# Transmitter_MD.net
KiCad netlist of a schematic drawn in Altium Designer
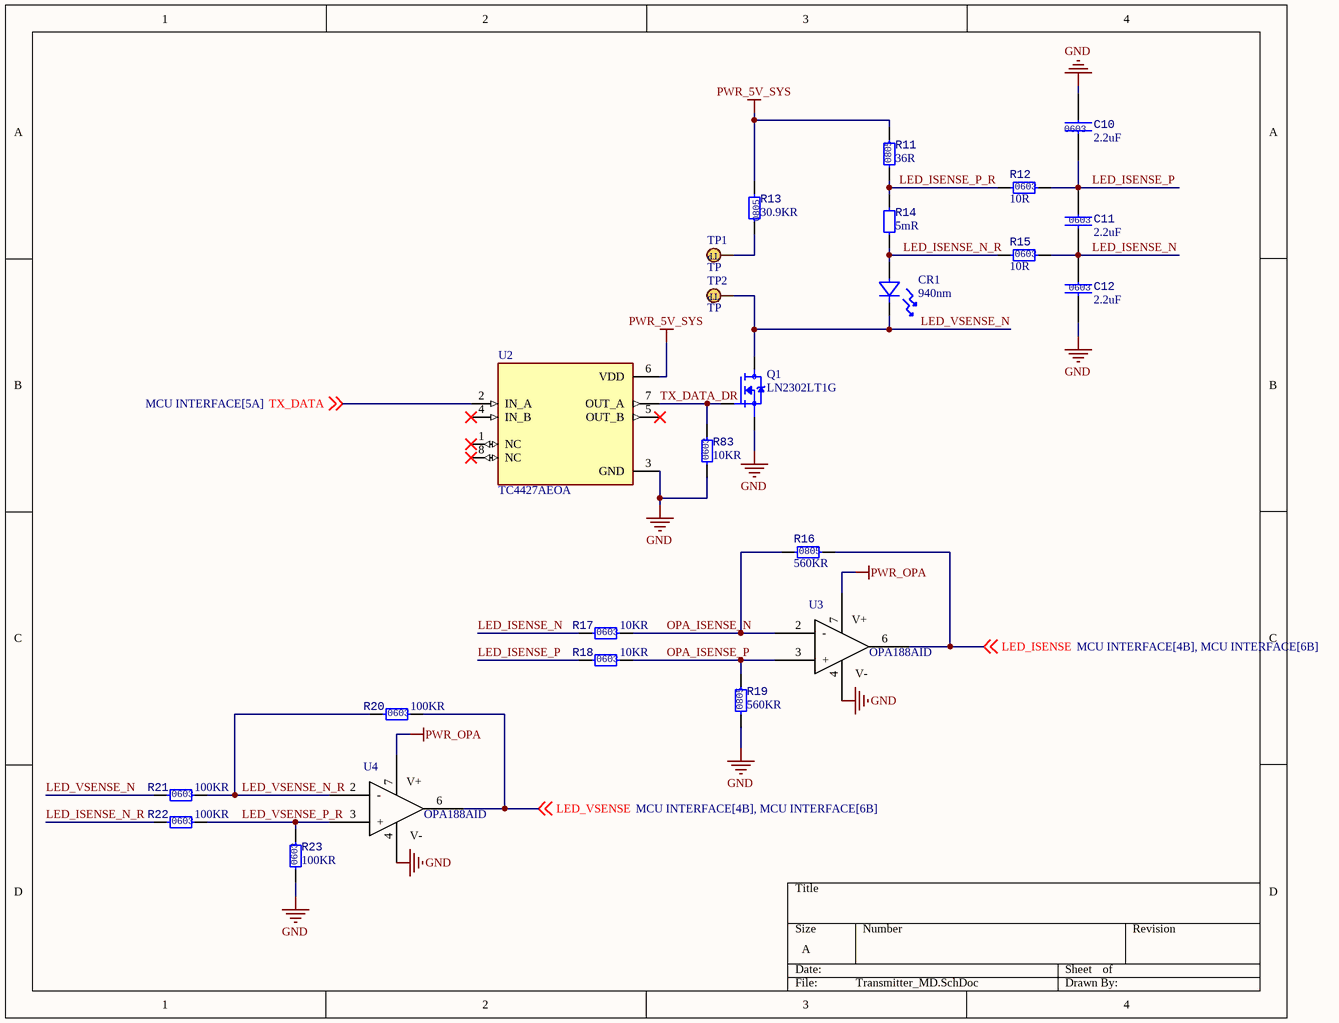
[diagram p0: Transmitter_MD.SchDoc]

(export (version "E")
  (design (tool "Eeschema 10.0.6"))
  (components
    (comp (ref "C10")
      (value "2.2uF")
      (footprint "CAPCER 0603 SMD")
      (description "Tụ Gốm 0603 2.2uF 50V")
      (fields (field (name "SIZE") "0603"))
      (libsource (lib "Database_Libs2") (part "CAPACITOR"))
    )
    (comp (ref "C11")
      (value "2.2uF")
      (footprint "CAPCER 0603 SMD")
      (description "Tụ Gốm 0603 2.2uF 50V")
      (fields (field (name "SIZE") "0603"))
      (libsource (lib "Database_Libs2") (part "CAPACITOR"))
    )
    (comp (ref "C12")
      (value "2.2uF")
      (footprint "CAPCER 0603 SMD")
      (description "Tụ Gốm 0603 2.2uF 50V")
      (fields (field (name "SIZE") "0603"))
      (libsource (lib "Database_Libs2") (part "CAPACITOR"))
    )
    (comp (ref "CR1")
      (value "940nm")
      (footprint "TSAL6100")
      (fields (field (name "Comment") "LED IR 940nm"))
      (libsource (lib "Database_Libs2") (part "TSAL6100"))
    )
    (comp (ref "Q1")
      (value "LN2302LT1G")
      (footprint "SOT23-3")
      (description "LN2302LT1G MOSFET Kênh N 20V 2.3A SOT-23-3")
      (fields (field (name "Comment") "NMOS"))
      (libsource (lib "Database_Libs2") (part "N_MOS"))
    )
    (comp (ref "R11")
      (value "36R")
      (footprint "RESC 0805 SMD")
      (fields (field (name "SIZE") "0805"))
      (libsource (lib "") (part "RESISTOR_1"))
    )
    (comp (ref "R12")
      (value "10R")
      (footprint "RESC 0603(1608) SMD")
      (description "Điện Trở 10 Ohm 0603 1%")
      (fields (field (name "SIZE") "0603"))
      (libsource (lib "Database_Libs2") (part "RESISTOR"))
    )
    (comp (ref "R13")
      (value "30.9KR")
      (footprint "RESC 0805 SMD")
      (description "Điện Trở 30.9 KOhm 0805 1%")
      (fields (field (name "SIZE") "0805"))
      (libsource (lib "") (part "RESISTOR_2"))
    )
    (comp (ref "R14") (value "5mR") (footprint "RS_P10_D1P5") (libsource (lib "") (part "RESISTOR_1")))
    (comp (ref "R15")
      (value "10R")
      (footprint "RESC 0603(1608) SMD")
      (description "Điện Trở 10 Ohm 0603 1%")
      (fields (field (name "SIZE") "0603"))
      (libsource (lib "Database_Libs2") (part "RESISTOR"))
    )
    (comp (ref "R16")
      (value "560KR")
      (footprint "RESC 0805 SMD")
      (fields (field (name "SIZE") "0805"))
      (libsource (lib "Database_Libs2") (part "RESISTOR"))
    )
    (comp (ref "R17")
      (value "10KR")
      (footprint "RESC 0603(1608) SMD")
      (description "RESISTOR SMD 10KR OHM 1% 100mW 0603")
      (fields (field (name "SIZE") "0603") (field (name "TOLERANCE") "1%"))
      (libsource (lib "Database_Libs1") (part "RESISTOR"))
    )
    (comp (ref "R18")
      (value "10KR")
      (footprint "RESC 0603(1608) SMD")
      (description "RESISTOR SMD 10KR OHM 1% 100mW 0603")
      (fields (field (name "SIZE") "0603") (field (name "TOLERANCE") "1%"))
      (libsource (lib "Database_Libs1") (part "RESISTOR"))
    )
    (comp (ref "R19")
      (value "560KR")
      (footprint "RESC 0805 SMD")
      (fields (field (name "SIZE") "0805"))
      (libsource (lib "") (part "RESISTOR_1"))
    )
    (comp (ref "R20")
      (value "100KR")
      (footprint "RESC 0603(1608) SMD")
      (description "RESISTOR SMD 100KR OHM 1% 100mW 0603")
      (fields (field (name "SIZE") "0603") (field (name "TOLERANCE") "1%"))
      (libsource (lib "Database_Libs1") (part "RESISTOR"))
    )
    (comp (ref "R21")
      (value "100KR")
      (footprint "RESC 0603(1608) SMD")
      (description "RESISTOR SMD 100KR OHM 1% 100mW 0603")
      (fields (field (name "SIZE") "0603") (field (name "TOLERANCE") "1%"))
      (libsource (lib "Database_Libs1") (part "RESISTOR"))
    )
    (comp (ref "R22")
      (value "100KR")
      (footprint "RESC 0603(1608) SMD")
      (description "RESISTOR SMD 100KR OHM 1% 100mW 0603")
      (fields (field (name "SIZE") "0603") (field (name "TOLERANCE") "1%"))
      (libsource (lib "Database_Libs1") (part "RESISTOR"))
    )
    (comp (ref "R23")
      (value "100KR")
      (footprint "RESC 0603(1608) SMD")
      (description "RESISTOR SMD 100KR OHM 1% 100mW 0603")
      (fields (field (name "SIZE") "0603") (field (name "TOLERANCE") "1%"))
      (libsource (lib "") (part "RESISTOR_1"))
    )
    (comp (ref "R83")
      (value "10KR")
      (footprint "RESC 0603(1608) SMD")
      (description "RESISTOR SMD 10KR OHM 1% 100mW 0603")
      (fields (field (name "SIZE") "0603") (field (name "TOLERANCE") "1%"))
      (libsource (lib "") (part "RESISTOR_1"))
    )
    (comp (ref "TP1")
      (value "TP")
      (footprint "TP_THT_1P0")
      (fields (field (name "Comment") "TEST POINT"))
      (libsource (lib "Database_Libs2") (part "Test_point"))
    )
    (comp (ref "TP2")
      (value "TP")
      (footprint "TP_THT_1P0")
      (fields (field (name "Comment") "TEST POINT"))
      (libsource (lib "Database_Libs2") (part "Test_point"))
    )
    (comp (ref "U2")
      (value "TC4427AEOA")
      (footprint "8-SOIC-OPA")
      (libsource (lib "Database_Libs2") (part "TC4427AEOA"))
    )
    (comp (ref "U3")
      (value "OPA188AID")
      (footprint "8-SOIC-OPA")
      (description "Zero-Drift Amplifier 1 Circuit Rail-to-Rail 8-SOIC")
      (libsource (lib "Database_Libs1") (part "OPA188AID"))
    )
    (comp (ref "U4")
      (value "OPA188AID")
      (footprint "8-SOIC-OPA")
      (description "Zero-Drift Amplifier 1 Circuit Rail-to-Rail 8-SOIC")
      (libsource (lib "Database_Libs1") (part "OPA188AID"))
    )
  )
  (nets
    (net (code "1") (name "/LED_ISENSE_N") (class "Default")
      (node (ref "C11") (pin "2") (pinfunction "2_2") (pintype "passive"))
      (node (ref "C12") (pin "1") (pinfunction "1_1") (pintype "passive"))
      (node (ref "R15") (pin "2") (pinfunction "2_2") (pintype "passive"))
      (node (ref "R17") (pin "1") (pinfunction "1_1") (pintype "passive"))
    )
    (net (code "2") (name "/LED_ISENSE_N_R") (class "Default")
      (node (ref "CR1") (pin "A") (pinfunction "A_A") (pintype "passive"))
      (node (ref "R14") (pin "1") (pinfunction "1_1") (pintype "passive"))
      (node (ref "R15") (pin "1") (pinfunction "1_1") (pintype "passive"))
      (node (ref "R22") (pin "1") (pinfunction "1_1") (pintype "passive"))
    )
    (net (code "3") (name "/LED_ISENSE_P") (class "Default")
      (node (ref "C10") (pin "1") (pinfunction "1_1") (pintype "passive"))
      (node (ref "C11") (pin "1") (pinfunction "1_1") (pintype "passive"))
      (node (ref "R12") (pin "2") (pinfunction "2_2") (pintype "passive"))
      (node (ref "R18") (pin "1") (pinfunction "1_1") (pintype "passive"))
    )
    (net (code "4") (name "/LED_ISENSE_P_R") (class "Default")
      (node (ref "R11") (pin "1") (pinfunction "1_1") (pintype "passive"))
      (node (ref "R12") (pin "1") (pinfunction "1_1") (pintype "passive"))
      (node (ref "R14") (pin "2") (pinfunction "2_2") (pintype "passive"))
    )
    (net (code "5") (name "/LED_VSENSE_N") (class "Default")
      (node (ref "CR1") (pin "K") (pinfunction "K_K") (pintype "passive"))
      (node (ref "Q1") (pin "3") (pinfunction "D_3") (pintype "passive"))
      (node (ref "R21") (pin "1") (pinfunction "1_1") (pintype "passive"))
      (node (ref "TP2") (pin "1") (pinfunction "1_1") (pintype "passive"))
    )
    (net (code "6") (name "/LED_VSENSE_N_R") (class "Default")
      (node (ref "R20") (pin "1") (pinfunction "1_1") (pintype "passive"))
      (node (ref "R21") (pin "2") (pinfunction "2_2") (pintype "passive"))
      (node (ref "U4") (pin "2") (pinfunction "-_2") (pintype "passive"))
    )
    (net (code "7") (name "/LED_VSENSE_P_R") (class "Default")
      (node (ref "R22") (pin "2") (pinfunction "2_2") (pintype "passive"))
      (node (ref "R23") (pin "2") (pinfunction "2_2") (pintype "passive"))
      (node (ref "U4") (pin "3") (pinfunction "+_3") (pintype "passive"))
    )
    (net (code "8") (name "/OPA_ISENSE_N") (class "Default")
      (node (ref "R16") (pin "1") (pinfunction "1_1") (pintype "passive"))
      (node (ref "R17") (pin "2") (pinfunction "2_2") (pintype "passive"))
      (node (ref "U3") (pin "2") (pinfunction "-_2") (pintype "passive"))
    )
    (net (code "9") (name "/OPA_ISENSE_P") (class "Default")
      (node (ref "R18") (pin "2") (pinfunction "2_2") (pintype "passive"))
      (node (ref "R19") (pin "2") (pinfunction "2_2") (pintype "passive"))
      (node (ref "U3") (pin "3") (pinfunction "+_3") (pintype "passive"))
    )
    (net (code "10") (name "/TX_DATA_DR") (class "Default")
      (node (ref "Q1") (pin "1") (pinfunction "G_1") (pintype "passive"))
      (node (ref "R83") (pin "2") (pinfunction "2_2") (pintype "passive"))
      (node (ref "U2") (pin "7") (pinfunction "OUT_A_7") (pintype "output"))
    )
    (net (code "11") (name "GND") (class "Default")
      (node (ref "C10") (pin "2") (pinfunction "2_2") (pintype "passive"))
      (node (ref "C12") (pin "2") (pinfunction "2_2") (pintype "passive"))
      (node (ref "Q1") (pin "2") (pinfunction "S_2") (pintype "passive"))
      (node (ref "R19") (pin "1") (pinfunction "1_1") (pintype "passive"))
      (node (ref "R23") (pin "1") (pinfunction "1_1") (pintype "passive"))
      (node (ref "R83") (pin "1") (pinfunction "1_1") (pintype "passive"))
      (node (ref "U2") (pin "3") (pinfunction "GND_3") (pintype "power_in"))
      (node (ref "U3") (pin "4") (pinfunction "GND_4") (pintype "passive"))
      (node (ref "U4") (pin "4") (pinfunction "GND_4") (pintype "passive"))
    )
    (net (code "12") (name "LED_ISENSE") (class "Default")
      (node (ref "R16") (pin "2") (pinfunction "2_2") (pintype "passive"))
      (node (ref "U3") (pin "6") (pinfunction "OUT_1_6") (pintype "passive"))
    )
    (net (code "13") (name "LED_VSENSE") (class "Default")
      (node (ref "R20") (pin "2") (pinfunction "2_2") (pintype "passive"))
      (node (ref "U4") (pin "6") (pinfunction "OUT_1_6") (pintype "passive"))
    )
    (net (code "14") (name "Net-(R13-Pad2)") (class "Default")
      (node (ref "R13") (pin "2") (pinfunction "2_2") (pintype "passive"))
      (node (ref "TP1") (pin "1") (pinfunction "1_1") (pintype "passive"))
    )
    (net (code "15") (name "PWR_5V_SYS") (class "Default")
      (node (ref "R11") (pin "2") (pinfunction "2_2") (pintype "passive"))
      (node (ref "R13") (pin "1") (pinfunction "1_1") (pintype "passive"))
      (node (ref "U2") (pin "6") (pinfunction "VDD_6") (pintype "power_in"))
    )
    (net (code "16") (name "PWR_OPA") (class "Default")
      (node (ref "U3") (pin "7") (pinfunction "VCC_7") (pintype "passive"))
      (node (ref "U4") (pin "7") (pinfunction "VCC_7") (pintype "passive"))
    )
    (net (code "17") (name "TX_DATA") (class "Default")
      (node (ref "U2") (pin "2") (pinfunction "IN_A_2") (pintype "input"))
    )
    (net (code "18") (name "unconnected-(U2-IN_B-Pad4)") (class "Default")
      (node (ref "U2") (pin "4") (pinfunction "IN_B_4") (pintype "input+no_connect"))
    )
    (net (code "19") (name "unconnected-(U2-NC-Pad1)") (class "Default")
      (node (ref "U2") (pin "1") (pinfunction "NC_1") (pintype "bidirectional+no_connect"))
    )
    (net (code "20") (name "unconnected-(U2-NC-Pad8)") (class "Default")
      (node (ref "U2") (pin "8") (pinfunction "NC_8") (pintype "bidirectional+no_connect"))
    )
    (net (code "21") (name "unconnected-(U2-OUT_B-Pad5)") (class "Default")
      (node (ref "U2") (pin "5") (pinfunction "OUT_B_5") (pintype "output+no_connect"))
    )
  )
)
